# fet-dd-charger-20mm-mk-1_0-bottom.net
KiCad netlist of a schematic drawn in EAGLE
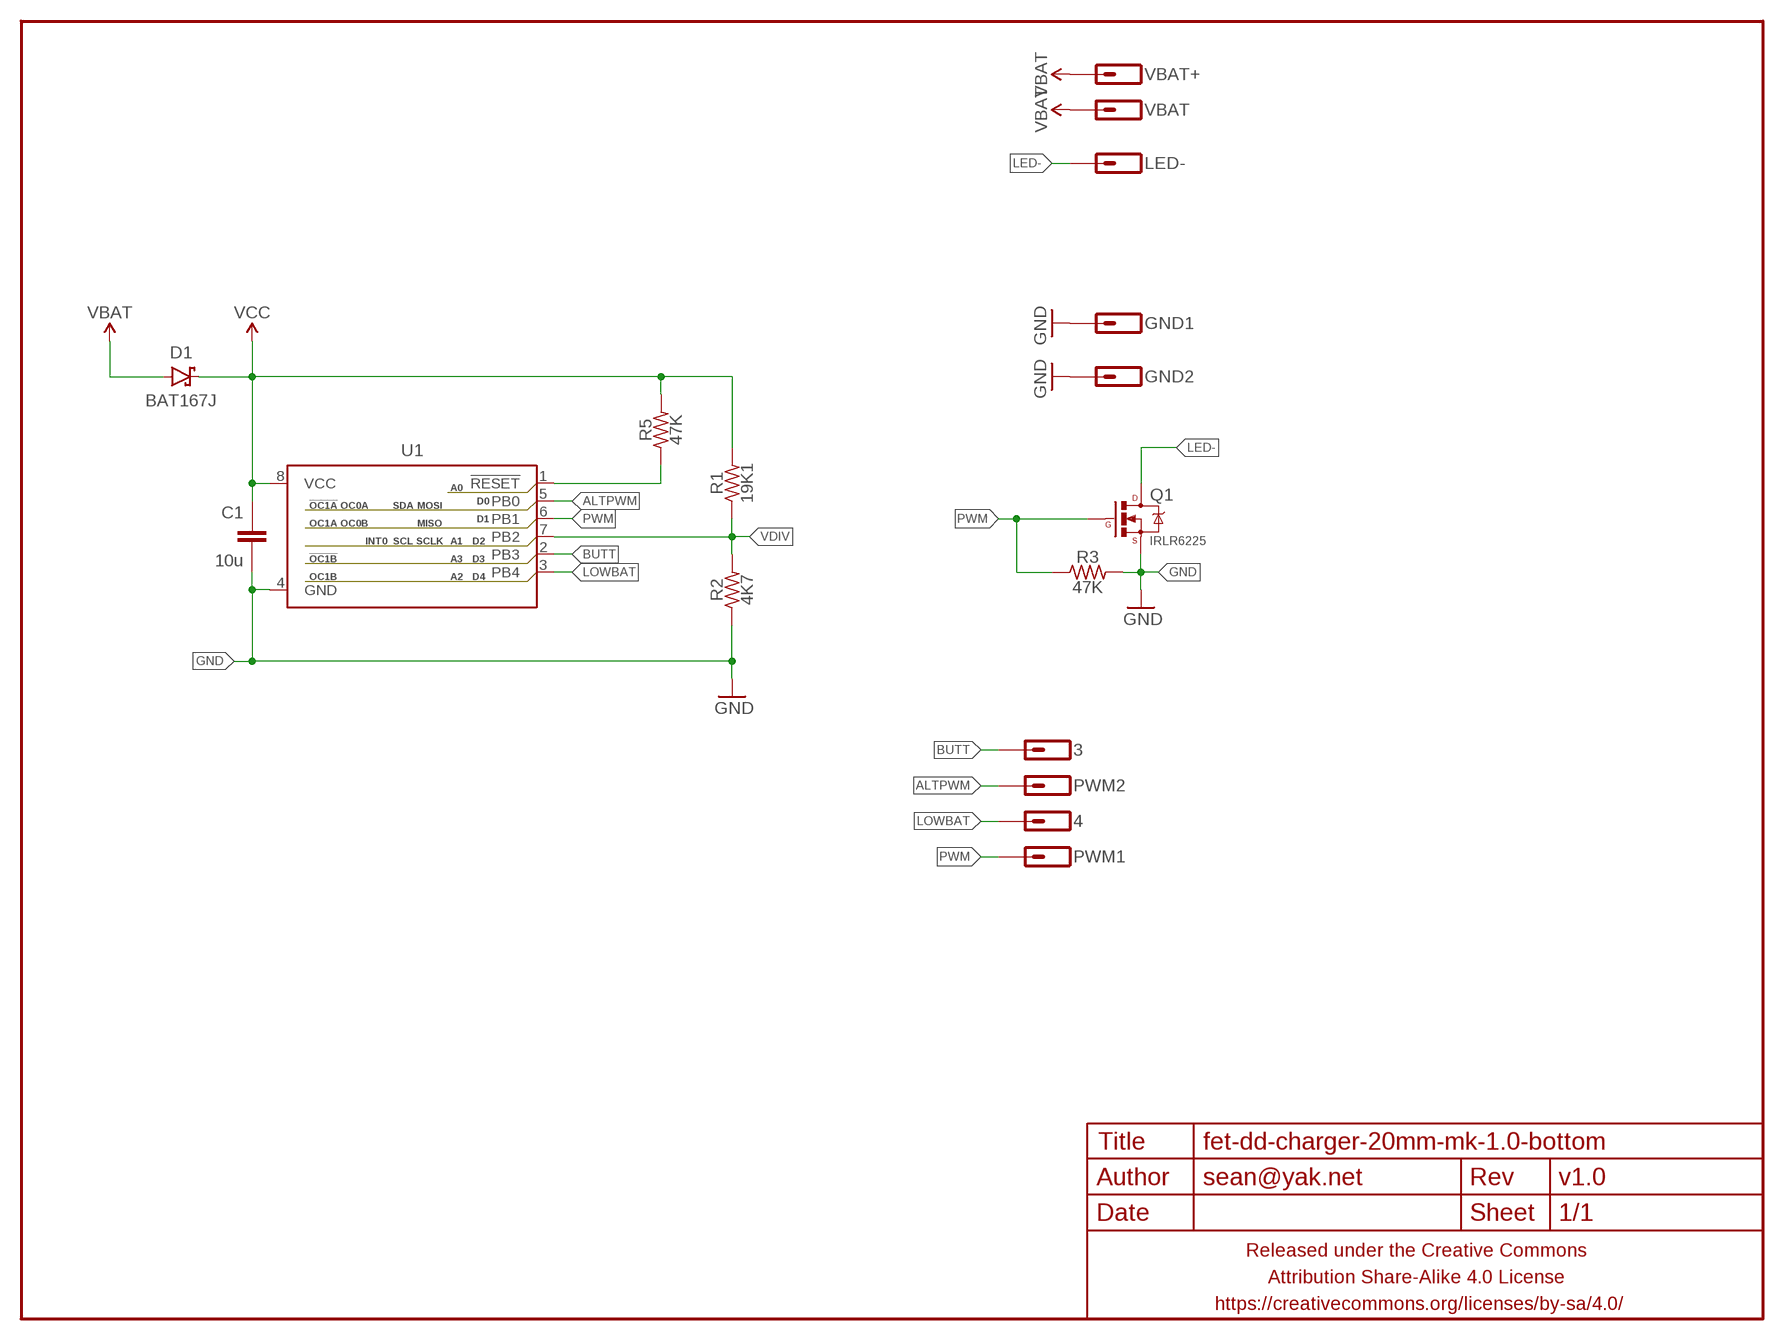
[diagram p0: schematic, sheet 1]

(export (version "E")
  (design (tool "Eeschema 10.0.6"))
  (components
    (comp (ref "3")
      (value "M01SMD-1MM-DIA-NS")
      (footprint "eagle-import:1X01-SMD-1MM-DIA-NS")
      (libsource (lib "eagle-import") (part "M01SMD-1MM-DIA-NS"))
    )
    (comp (ref "4")
      (value "M01SMD-1MM-DIA-NS")
      (footprint "eagle-import:1X01-SMD-1MM-DIA-NS")
      (libsource (lib "eagle-import") (part "M01SMD-1MM-DIA-NS"))
    )
    (comp (ref "C1")
      (value "10u")
      (footprint "eagle-import:C0603-TIGHTER")
      (libsource (lib "eagle-import") (part "CAPACITOR-CERAMICC0603-TIGHTER"))
    )
    (comp (ref "D1")
      (value "BAT167J")
      (footprint "eagle-import:SOD123-SCHOTTKY")
      (libsource (lib "eagle-import") (part "DIODE-SCHOTTKYSOD123"))
    )
    (comp (ref "FRAME1")
      (value "FRAME-LETTERNO_PACKAGE")
      (footprint "eagle-import:DUMMY")
      (fields (field (name "DESIGNER") "sean@yak.net") (field (name "VERSION") "v1.0"))
      (libsource (lib "eagle-import") (part "FRAME-LETTERNO_PACKAGE"))
    )
    (comp (ref "GND1")
      (value "M01PTH_2MM")
      (footprint "eagle-import:1X01_2MM")
      (libsource (lib "eagle-import") (part "M01PTH_2MM"))
    )
    (comp (ref "GND2")
      (value "M01PTH_2MM")
      (footprint "eagle-import:1X01_2MM")
      (libsource (lib "eagle-import") (part "M01PTH_2MM"))
    )
    (comp (ref "LED-")
      (value "M01PTH_2MM")
      (footprint "eagle-import:1X01_2MM")
      (libsource (lib "eagle-import") (part "M01PTH_2MM"))
    )
    (comp (ref "PWM1")
      (value "M01SMD-1MM-DIA-NS")
      (footprint "eagle-import:1X01-SMD-1MM-DIA-NS")
      (libsource (lib "eagle-import") (part "M01SMD-1MM-DIA-NS"))
    )
    (comp (ref "PWM2")
      (value "M01SMD-1MM-DIA-NS")
      (footprint "eagle-import:1X01-SMD-1MM-DIA-NS")
      (libsource (lib "eagle-import") (part "M01SMD-1MM-DIA-NS"))
    )
    (comp (ref "Q1")
      (value "IRLR6225")
      (footprint "eagle-import:POWERPACK-SO-8")
      (libsource (lib "eagle-import") (part "MOSFET-NCHANNELSIR800DP"))
    )
    (comp (ref "R1")
      (value "19K1")
      (footprint "eagle-import:R0603-TIGHTER")
      (libsource (lib "eagle-import") (part "RESISTORR0603-TIGHTER"))
    )
    (comp (ref "R2")
      (value "4K7")
      (footprint "eagle-import:R0603-TIGHTER")
      (libsource (lib "eagle-import") (part "RESISTORR0603-TIGHTER"))
    )
    (comp (ref "R3")
      (value "47K")
      (footprint "eagle-import:R0603-TIGHTER")
      (libsource (lib "eagle-import") (part "RESISTORR0603-TIGHTER"))
    )
    (comp (ref "R5")
      (value "47K")
      (footprint "eagle-import:R0603-TIGHTER")
      (libsource (lib "eagle-import") (part "RESISTORR0603-TIGHTER"))
    )
    (comp (ref "U1")
      (value "ATTINY13SOIC-NARROWPADS")
      (footprint "eagle-import:SO08-NARROWER")
      (libsource (lib "eagle-import") (part "ATTINY13SOIC-NARROWPADS"))
    )
    (comp (ref "VBAT")
      (value "M01PTH_2MM")
      (footprint "eagle-import:1X01_2MM")
      (libsource (lib "eagle-import") (part "M01PTH_2MM"))
    )
    (comp (ref "VBAT+")
      (value "M01NOSTOP-CANTSTOP-DONTKNOWHOWTOSTOP")
      (footprint "eagle-import:1X01_SMD_NOSTOP_NOSILK")
      (libsource (lib "eagle-import") (part "M01NOSTOP-CANTSTOP-DONTKNOWHOWTOSTOP"))
    )
  )
  (nets
    (net (code "1") (name "ALTPWM") (class "Default")
      (node (ref "PWM2") (pin "P$1") (pinfunction "1_P$1") (pintype "passive"))
      (node (ref "U1") (pin "5") (pinfunction "PB0_5") (pintype "bidirectional"))
    )
    (net (code "2") (name "BUTT") (class "Default")
      (node (ref "3") (pin "P$1") (pinfunction "1_P$1") (pintype "passive"))
      (node (ref "U1") (pin "2") (pinfunction "PB3_2") (pintype "bidirectional"))
    )
    (net (code "3") (name "GND") (class "Default")
      (node (ref "C1") (pin "2") (pinfunction "2_2") (pintype "passive"))
      (node (ref "GND1") (pin "1") (pinfunction "1_1") (pintype "passive"))
      (node (ref "GND2") (pin "1") (pinfunction "1_1") (pintype "passive"))
      (node (ref "Q1") (pin "1") (pinfunction "S_1") (pintype "passive"))
      (node (ref "Q1") (pin "2") (pinfunction "S_2") (pintype "passive"))
      (node (ref "Q1") (pin "3") (pinfunction "S_3") (pintype "passive"))
      (node (ref "R2") (pin "1") (pinfunction "1_1") (pintype "passive"))
      (node (ref "R3") (pin "2") (pinfunction "2_2") (pintype "passive"))
      (node (ref "U1") (pin "4") (pinfunction "GND_4") (pintype "bidirectional"))
    )
    (net (code "4") (name "LED-") (class "Default")
      (node (ref "LED-") (pin "1") (pinfunction "1_1") (pintype "passive"))
      (node (ref "Q1") (pin "5678") (pinfunction "D_5678") (pintype "passive"))
    )
    (net (code "5") (name "LOWBAT") (class "Default")
      (node (ref "4") (pin "P$1") (pinfunction "1_P$1") (pintype "passive"))
      (node (ref "U1") (pin "3") (pinfunction "PB4_3") (pintype "bidirectional"))
    )
    (net (code "6") (name "Net-(U1-~{RESET})") (class "Default")
      (node (ref "R5") (pin "1") (pinfunction "1_1") (pintype "passive"))
      (node (ref "U1") (pin "1") (pinfunction "~{RESET}_1") (pintype "bidirectional"))
    )
    (net (code "7") (name "PWM") (class "Default")
      (node (ref "PWM1") (pin "P$1") (pinfunction "1_P$1") (pintype "passive"))
      (node (ref "Q1") (pin "4") (pinfunction "G_4") (pintype "passive"))
      (node (ref "R3") (pin "1") (pinfunction "1_1") (pintype "passive"))
      (node (ref "U1") (pin "6") (pinfunction "PB1_6") (pintype "bidirectional"))
    )
    (net (code "8") (name "VBAT") (class "Default")
      (node (ref "D1") (pin "A") (pinfunction "A_A") (pintype "passive"))
      (node (ref "VBAT") (pin "1") (pinfunction "1_1") (pintype "passive"))
      (node (ref "VBAT+") (pin "1") (pinfunction "1_1") (pintype "passive"))
    )
    (net (code "9") (name "VCC") (class "Default")
      (node (ref "C1") (pin "1") (pinfunction "1_1") (pintype "passive"))
      (node (ref "D1") (pin "C") (pinfunction "C_C") (pintype "passive"))
      (node (ref "R1") (pin "2") (pinfunction "2_2") (pintype "passive"))
      (node (ref "R5") (pin "2") (pinfunction "2_2") (pintype "passive"))
      (node (ref "U1") (pin "8") (pinfunction "VCC_8") (pintype "bidirectional"))
    )
    (net (code "10") (name "VDIV") (class "Default")
      (node (ref "R1") (pin "1") (pinfunction "1_1") (pintype "passive"))
      (node (ref "R2") (pin "2") (pinfunction "2_2") (pintype "passive"))
      (node (ref "U1") (pin "7") (pinfunction "PB2_7") (pintype "bidirectional"))
    )
  )
)
